# SimulatorT2InterfaceRevD.net
KiCad netlist of a schematic drawn in EAGLE
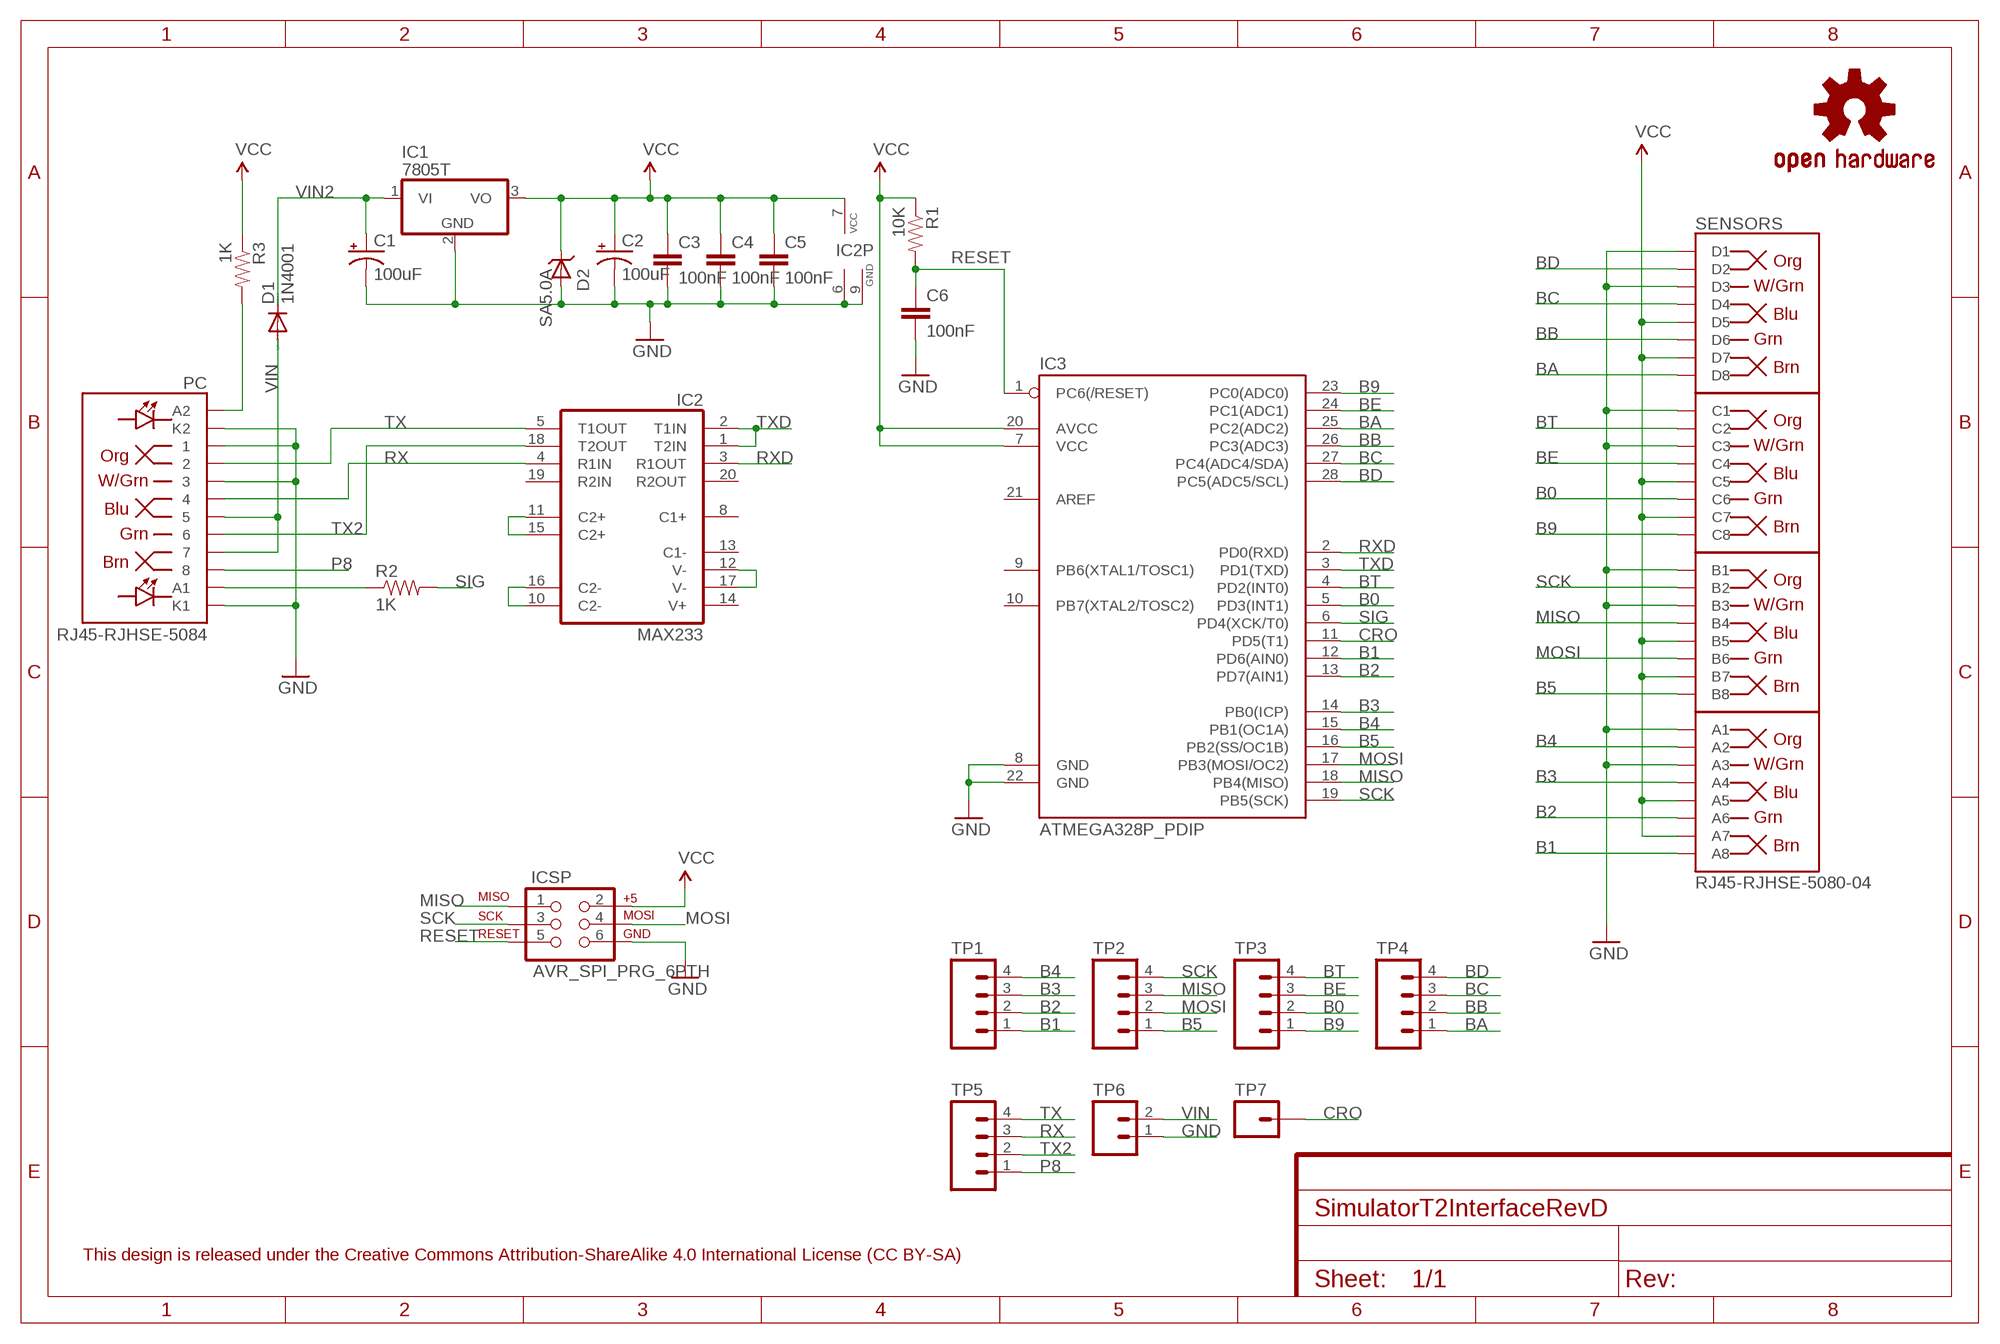
[diagram p0: schematic, sheet 1]

(export (version "E")
  (design (tool "Eeschema 10.0.6"))
  (components
    (comp (ref "C1")
      (value "100uF")
      (footprint "eagle-import:CPOL-RADIAL-100UF-25V")
      (libsource (lib "eagle-import") (part "CAP_POLPTH1"))
    )
    (comp (ref "C2")
      (value "100uF")
      (footprint "eagle-import:CPOL-RADIAL-100UF-25V")
      (libsource (lib "eagle-import") (part "CAP_POLPTH1"))
    )
    (comp (ref "C3")
      (value "100nF")
      (footprint "eagle-import:CAP-PTH-SMALL")
      (libsource (lib "eagle-import") (part "CAPPTH"))
    )
    (comp (ref "C4")
      (value "100nF")
      (footprint "eagle-import:CAP-PTH-SMALL")
      (libsource (lib "eagle-import") (part "CAPPTH"))
    )
    (comp (ref "C5")
      (value "100nF")
      (footprint "eagle-import:CAP-PTH-SMALL")
      (libsource (lib "eagle-import") (part "CAPPTH"))
    )
    (comp (ref "C6")
      (value "100nF")
      (footprint "eagle-import:CAP-PTH-SMALL")
      (libsource (lib "eagle-import") (part "CAPPTH"))
    )
    (comp (ref "D1")
      (value "1N4001")
      (footprint "eagle-import:DO41_DIODE")
      (libsource (lib "eagle-import") (part "1N4001"))
    )
    (comp (ref "D2")
      (value "SA5.0A")
      (footprint "eagle-import:DO41_TVS_UNI")
      (libsource (lib "eagle-import") (part "SA5.0A"))
    )
    (comp (ref "IC1")
      (value "7805T")
      (footprint "eagle-import:TO220H+TSR")
      (libsource (lib "eagle-import") (part "7805T"))
    )
    (comp (ref "IC2")
      (value "MAX233")
      (footprint "eagle-import:DIL20")
      (fields (field (name "MPN") "MAX233ACPP+G36"))
      (libsource (lib "eagle-import") (part "MAX233"))
    )
    (comp (ref "IC3")
      (value "ATMEGA328P_PDIP")
      (footprint "eagle-import:DIL28-3")
      (libsource (lib "eagle-import") (part "ATMEGA328P_PDIP"))
    )
    (comp (ref "ICSP")
      (value "AVR_SPI_PRG_6PTH")
      (footprint "eagle-import:2X3")
      (libsource (lib "eagle-import") (part "AVR_SPI_PRG_6PTH"))
    )
    (comp (ref "LOGO1")
      (value "OSHW-LOGOS")
      (footprint "eagle-import:OSHW-LOGO-S")
      (libsource (lib "eagle-import") (part "OSHW-LOGOS"))
    )
    (comp (ref "PC")
      (value "RJ45-RJHSE-5084")
      (footprint "eagle-import:RJ45-RJHSE-5084")
      (libsource (lib "eagle-import") (part "RJ45-RJHSE-5084"))
    )
    (comp (ref "R1")
      (value "10K")
      (footprint "eagle-import:AXIAL-0.4")
      (libsource (lib "eagle-import") (part "RESISTORPTH-1/4W"))
    )
    (comp (ref "R2")
      (value "1K")
      (footprint "eagle-import:AXIAL-0.4")
      (libsource (lib "eagle-import") (part "RESISTORPTH-1/4W"))
    )
    (comp (ref "R3")
      (value "1K")
      (footprint "eagle-import:AXIAL-0.4")
      (libsource (lib "eagle-import") (part "RESISTORPTH-1/4W"))
    )
    (comp (ref "SENSORS")
      (value "RJ45-RJHSE-5080-04")
      (footprint "eagle-import:RJ45-RJHSE-5080-04")
      (libsource (lib "eagle-import") (part "RJ45-RJHSE-5080-04"))
    )
    (comp (ref "TP1")
      (value "M04PTH")
      (footprint "eagle-import:1X04")
      (libsource (lib "eagle-import") (part "M04PTH"))
    )
    (comp (ref "TP2")
      (value "M04PTH")
      (footprint "eagle-import:1X04")
      (libsource (lib "eagle-import") (part "M04PTH"))
    )
    (comp (ref "TP3")
      (value "M04PTH")
      (footprint "eagle-import:1X04")
      (libsource (lib "eagle-import") (part "M04PTH"))
    )
    (comp (ref "TP4")
      (value "M04PTH")
      (footprint "eagle-import:1X04")
      (libsource (lib "eagle-import") (part "M04PTH"))
    )
    (comp (ref "TP5")
      (value "M04PTH")
      (footprint "eagle-import:1X04")
      (libsource (lib "eagle-import") (part "M04PTH"))
    )
    (comp (ref "TP6")
      (value "M02PTH")
      (footprint "eagle-import:1X02")
      (libsource (lib "eagle-import") (part "M02PTH"))
    )
    (comp (ref "TP7")
      (value "M01PTH")
      (footprint "eagle-import:1X01")
      (libsource (lib "eagle-import") (part "M01PTH"))
    )
  )
  (nets
    (net (code "1") (name "/B0") (class "Default")
      (node (ref "IC3") (pin "5") (pinfunction "PD3(INT1)_5") (pintype "bidirectional"))
      (node (ref "SENSORS") (pin "C6") (pinfunction "C6_C6") (pintype "bidirectional"))
      (node (ref "TP3") (pin "2") (pinfunction "2_2") (pintype "passive"))
    )
    (net (code "2") (name "/B1") (class "Default")
      (node (ref "IC3") (pin "12") (pinfunction "PD6(AIN0)_12") (pintype "bidirectional"))
      (node (ref "SENSORS") (pin "A8") (pinfunction "A8_A8") (pintype "bidirectional"))
      (node (ref "TP1") (pin "1") (pinfunction "1_1") (pintype "passive"))
    )
    (net (code "3") (name "/B2") (class "Default")
      (node (ref "IC3") (pin "13") (pinfunction "PD7(AIN1)_13") (pintype "bidirectional"))
      (node (ref "SENSORS") (pin "A6") (pinfunction "A6_A6") (pintype "bidirectional"))
      (node (ref "TP1") (pin "2") (pinfunction "2_2") (pintype "passive"))
    )
    (net (code "4") (name "/B3") (class "Default")
      (node (ref "IC3") (pin "14") (pinfunction "PB0(ICP)_14") (pintype "bidirectional"))
      (node (ref "SENSORS") (pin "A4") (pinfunction "A4_A4") (pintype "bidirectional"))
      (node (ref "TP1") (pin "3") (pinfunction "3_3") (pintype "passive"))
    )
    (net (code "5") (name "/B4") (class "Default")
      (node (ref "IC3") (pin "15") (pinfunction "PB1(OC1A)_15") (pintype "bidirectional"))
      (node (ref "SENSORS") (pin "A2") (pinfunction "A2_A2") (pintype "bidirectional"))
      (node (ref "TP1") (pin "4") (pinfunction "4_4") (pintype "passive"))
    )
    (net (code "6") (name "/B5") (class "Default")
      (node (ref "IC3") (pin "16") (pinfunction "PB2(SS/OC1B)_16") (pintype "bidirectional"))
      (node (ref "SENSORS") (pin "B8") (pinfunction "B8_B8") (pintype "bidirectional"))
      (node (ref "TP2") (pin "1") (pinfunction "1_1") (pintype "passive"))
    )
    (net (code "7") (name "/B9") (class "Default")
      (node (ref "IC3") (pin "23") (pinfunction "PC0(ADC0)_23") (pintype "bidirectional"))
      (node (ref "SENSORS") (pin "C8") (pinfunction "C8_C8") (pintype "bidirectional"))
      (node (ref "TP3") (pin "1") (pinfunction "1_1") (pintype "passive"))
    )
    (net (code "8") (name "/BA") (class "Default")
      (node (ref "IC3") (pin "25") (pinfunction "PC2(ADC2)_25") (pintype "bidirectional"))
      (node (ref "SENSORS") (pin "D8") (pinfunction "D8_D8") (pintype "bidirectional"))
      (node (ref "TP4") (pin "1") (pinfunction "1_1") (pintype "passive"))
    )
    (net (code "9") (name "/BB") (class "Default")
      (node (ref "IC3") (pin "26") (pinfunction "PC3(ADC3)_26") (pintype "bidirectional"))
      (node (ref "SENSORS") (pin "D6") (pinfunction "D6_D6") (pintype "bidirectional"))
      (node (ref "TP4") (pin "2") (pinfunction "2_2") (pintype "passive"))
    )
    (net (code "10") (name "/BC") (class "Default")
      (node (ref "IC3") (pin "27") (pinfunction "PC4(ADC4/SDA)_27") (pintype "bidirectional"))
      (node (ref "SENSORS") (pin "D4") (pinfunction "D4_D4") (pintype "bidirectional"))
      (node (ref "TP4") (pin "3") (pinfunction "3_3") (pintype "passive"))
    )
    (net (code "11") (name "/BD") (class "Default")
      (node (ref "IC3") (pin "28") (pinfunction "PC5(ADC5/SCL)_28") (pintype "bidirectional"))
      (node (ref "SENSORS") (pin "D2") (pinfunction "D2_D2") (pintype "bidirectional"))
      (node (ref "TP4") (pin "4") (pinfunction "4_4") (pintype "passive"))
    )
    (net (code "12") (name "/BE") (class "Default")
      (node (ref "IC3") (pin "24") (pinfunction "PC1(ADC1)_24") (pintype "bidirectional"))
      (node (ref "SENSORS") (pin "C4") (pinfunction "C4_C4") (pintype "bidirectional"))
      (node (ref "TP3") (pin "3") (pinfunction "3_3") (pintype "passive"))
    )
    (net (code "13") (name "/BT") (class "Default")
      (node (ref "IC3") (pin "4") (pinfunction "PD2(INT0)_4") (pintype "bidirectional"))
      (node (ref "SENSORS") (pin "C2") (pinfunction "C2_C2") (pintype "bidirectional"))
      (node (ref "TP3") (pin "4") (pinfunction "4_4") (pintype "passive"))
    )
    (net (code "14") (name "/CRO") (class "Default")
      (node (ref "IC3") (pin "11") (pinfunction "PD5(T1)_11") (pintype "bidirectional"))
      (node (ref "TP7") (pin "1") (pinfunction "1_1") (pintype "passive"))
    )
    (net (code "15") (name "/MISO") (class "Default")
      (node (ref "IC3") (pin "18") (pinfunction "PB4(MISO)_18") (pintype "bidirectional"))
      (node (ref "ICSP") (pin "1") (pinfunction "1_1") (pintype "passive"))
      (node (ref "SENSORS") (pin "B4") (pinfunction "B4_B4") (pintype "bidirectional"))
      (node (ref "TP2") (pin "3") (pinfunction "3_3") (pintype "passive"))
    )
    (net (code "16") (name "/MOSI") (class "Default")
      (node (ref "IC3") (pin "17") (pinfunction "PB3(MOSI/OC2)_17") (pintype "bidirectional"))
      (node (ref "ICSP") (pin "4") (pinfunction "4_4") (pintype "passive"))
      (node (ref "SENSORS") (pin "B6") (pinfunction "B6_B6") (pintype "bidirectional"))
      (node (ref "TP2") (pin "2") (pinfunction "2_2") (pintype "passive"))
    )
    (net (code "17") (name "/P8") (class "Default")
      (node (ref "PC") (pin "8") (pinfunction "8_8") (pintype "bidirectional"))
      (node (ref "TP5") (pin "1") (pinfunction "1_1") (pintype "passive"))
    )
    (net (code "18") (name "/RESET") (class "Default")
      (node (ref "C6") (pin "1") (pinfunction "1_1") (pintype "passive"))
      (node (ref "IC3") (pin "1") (pinfunction "PC6(/RESET)_1") (pintype "bidirectional"))
      (node (ref "ICSP") (pin "5") (pinfunction "5_5") (pintype "passive"))
      (node (ref "R1") (pin "P$2") (pinfunction "2_P$2") (pintype "passive"))
    )
    (net (code "19") (name "/RX") (class "Default")
      (node (ref "IC2") (pin "4") (pinfunction "R1IN_4") (pintype "input"))
      (node (ref "PC") (pin "4") (pinfunction "4_4") (pintype "bidirectional"))
      (node (ref "TP5") (pin "3") (pinfunction "3_3") (pintype "passive"))
    )
    (net (code "20") (name "/RXD") (class "Default")
      (node (ref "IC2") (pin "3") (pinfunction "R1OUT_3") (pintype "output"))
      (node (ref "IC3") (pin "2") (pinfunction "PD0(RXD)_2") (pintype "bidirectional"))
    )
    (net (code "21") (name "/SCK") (class "Default")
      (node (ref "IC3") (pin "19") (pinfunction "PB5(SCK)_19") (pintype "bidirectional"))
      (node (ref "ICSP") (pin "3") (pinfunction "3_3") (pintype "passive"))
      (node (ref "SENSORS") (pin "B2") (pinfunction "B2_B2") (pintype "bidirectional"))
      (node (ref "TP2") (pin "4") (pinfunction "4_4") (pintype "passive"))
    )
    (net (code "22") (name "/SIG") (class "Default")
      (node (ref "IC3") (pin "6") (pinfunction "PD4(XCK/T0)_6") (pintype "bidirectional"))
      (node (ref "R2") (pin "P$2") (pinfunction "2_P$2") (pintype "passive"))
    )
    (net (code "23") (name "/TX") (class "Default")
      (node (ref "IC2") (pin "5") (pinfunction "T1OUT_5") (pintype "output"))
      (node (ref "PC") (pin "2") (pinfunction "2_2") (pintype "bidirectional"))
      (node (ref "TP5") (pin "4") (pinfunction "4_4") (pintype "passive"))
    )
    (net (code "24") (name "/TX2") (class "Default")
      (node (ref "IC2") (pin "18") (pinfunction "T2OUT_18") (pintype "output"))
      (node (ref "PC") (pin "6") (pinfunction "6_6") (pintype "bidirectional"))
      (node (ref "TP5") (pin "2") (pinfunction "2_2") (pintype "passive"))
    )
    (net (code "25") (name "/TXD") (class "Default")
      (node (ref "IC2") (pin "1") (pinfunction "T2IN_1") (pintype "input"))
      (node (ref "IC2") (pin "2") (pinfunction "T1IN_2") (pintype "input"))
      (node (ref "IC3") (pin "3") (pinfunction "PD1(TXD)_3") (pintype "bidirectional"))
    )
    (net (code "26") (name "/VIN") (class "Default")
      (node (ref "D1") (pin "A") (pinfunction "A_A") (pintype "passive"))
      (node (ref "PC") (pin "5") (pinfunction "5_5") (pintype "bidirectional"))
      (node (ref "PC") (pin "7") (pinfunction "7_7") (pintype "bidirectional"))
      (node (ref "TP6") (pin "2") (pinfunction "2_2") (pintype "passive"))
    )
    (net (code "27") (name "/VIN2") (class "Default")
      (node (ref "C1") (pin "1") (pinfunction "+_1") (pintype "passive"))
      (node (ref "D1") (pin "C") (pinfunction "C_C") (pintype "passive"))
      (node (ref "IC1") (pin "1") (pinfunction "VI_1") (pintype "input"))
    )
    (net (code "28") (name "GND") (class "Default")
      (node (ref "C1") (pin "2") (pinfunction "-_2") (pintype "passive"))
      (node (ref "C2") (pin "2") (pinfunction "-_2") (pintype "passive"))
      (node (ref "C3") (pin "2") (pinfunction "2_2") (pintype "passive"))
      (node (ref "C4") (pin "2") (pinfunction "2_2") (pintype "passive"))
      (node (ref "C5") (pin "2") (pinfunction "2_2") (pintype "passive"))
      (node (ref "C6") (pin "2") (pinfunction "2_2") (pintype "passive"))
      (node (ref "D2") (pin "ANODE") (pinfunction "ANODE_ANODE") (pintype "passive"))
      (node (ref "IC1") (pin "2") (pinfunction "GND_2") (pintype "passive"))
      (node (ref "IC2") (pin "6") (pinfunction "GND_6") (pintype "power_in"))
      (node (ref "IC2") (pin "9") (pinfunction "GND_9") (pintype "power_in"))
      (node (ref "IC3") (pin "22") (pinfunction "GND_22") (pintype "bidirectional"))
      (node (ref "IC3") (pin "8") (pinfunction "GND_8") (pintype "bidirectional"))
      (node (ref "ICSP") (pin "6") (pinfunction "6_6") (pintype "passive"))
      (node (ref "PC") (pin "1") (pinfunction "1_1") (pintype "bidirectional"))
      (node (ref "PC") (pin "3") (pinfunction "3_3") (pintype "bidirectional"))
      (node (ref "PC") (pin "K1") (pinfunction "K1_K1") (pintype "passive"))
      (node (ref "PC") (pin "K2") (pinfunction "K2_K2") (pintype "passive"))
      (node (ref "SENSORS") (pin "A1") (pinfunction "A1_A1") (pintype "bidirectional"))
      (node (ref "SENSORS") (pin "A3") (pinfunction "A3_A3") (pintype "bidirectional"))
      (node (ref "SENSORS") (pin "B1") (pinfunction "B1_B1") (pintype "bidirectional"))
      (node (ref "SENSORS") (pin "B3") (pinfunction "B3_B3") (pintype "bidirectional"))
      (node (ref "SENSORS") (pin "C1") (pinfunction "C1_C1") (pintype "bidirectional"))
      (node (ref "SENSORS") (pin "C3") (pinfunction "C3_C3") (pintype "bidirectional"))
      (node (ref "SENSORS") (pin "D1") (pinfunction "D1_D1") (pintype "bidirectional"))
      (node (ref "SENSORS") (pin "D3") (pinfunction "D3_D3") (pintype "bidirectional"))
      (node (ref "TP6") (pin "1") (pinfunction "1_1") (pintype "passive"))
    )
    (net (code "29") (name "Net-(IC2A-C2+-Pad11)") (class "Default")
      (node (ref "IC2") (pin "11") (pinfunction "C2+_11") (pintype "bidirectional"))
      (node (ref "IC2") (pin "15") (pinfunction "C2+_15") (pintype "bidirectional"))
    )
    (net (code "30") (name "Net-(IC2A-C2--Pad10)") (class "Default")
      (node (ref "IC2") (pin "10") (pinfunction "C2-_10") (pintype "bidirectional"))
      (node (ref "IC2") (pin "16") (pinfunction "C2-_16") (pintype "bidirectional"))
    )
    (net (code "31") (name "Net-(IC2A-V--Pad12)") (class "Default")
      (node (ref "IC2") (pin "12") (pinfunction "V-_12") (pintype "bidirectional"))
      (node (ref "IC2") (pin "17") (pinfunction "V-_17") (pintype "bidirectional"))
    )
    (net (code "32") (name "Net-(R2-1)") (class "Default")
      (node (ref "PC") (pin "A1") (pinfunction "A1_A1") (pintype "passive"))
      (node (ref "R2") (pin "P$1") (pinfunction "1_P$1") (pintype "passive"))
    )
    (net (code "33") (name "Net-(R3-2)") (class "Default")
      (node (ref "PC") (pin "A2") (pinfunction "A2_A2") (pintype "passive"))
      (node (ref "R3") (pin "P$2") (pinfunction "2_P$2") (pintype "passive"))
    )
    (net (code "34") (name "VCC") (class "Default")
      (node (ref "C2") (pin "1") (pinfunction "+_1") (pintype "passive"))
      (node (ref "C3") (pin "1") (pinfunction "1_1") (pintype "passive"))
      (node (ref "C4") (pin "1") (pinfunction "1_1") (pintype "passive"))
      (node (ref "C5") (pin "1") (pinfunction "1_1") (pintype "passive"))
      (node (ref "D2") (pin "CATHODE") (pinfunction "CATHODE_CATHODE") (pintype "passive"))
      (node (ref "IC1") (pin "3") (pinfunction "VO_3") (pintype "passive"))
      (node (ref "IC2") (pin "7") (pinfunction "VCC_7") (pintype "power_in"))
      (node (ref "IC3") (pin "20") (pinfunction "AVCC_20") (pintype "bidirectional"))
      (node (ref "IC3") (pin "7") (pinfunction "VCC_7") (pintype "bidirectional"))
      (node (ref "ICSP") (pin "2") (pinfunction "2_2") (pintype "passive"))
      (node (ref "R1") (pin "P$1") (pinfunction "1_P$1") (pintype "passive"))
      (node (ref "R3") (pin "P$1") (pinfunction "1_P$1") (pintype "passive"))
      (node (ref "SENSORS") (pin "A5") (pinfunction "A5_A5") (pintype "bidirectional"))
      (node (ref "SENSORS") (pin "A7") (pinfunction "A7_A7") (pintype "bidirectional"))
      (node (ref "SENSORS") (pin "B5") (pinfunction "B5_B5") (pintype "bidirectional"))
      (node (ref "SENSORS") (pin "B7") (pinfunction "B7_B7") (pintype "bidirectional"))
      (node (ref "SENSORS") (pin "C5") (pinfunction "C5_C5") (pintype "bidirectional"))
      (node (ref "SENSORS") (pin "C7") (pinfunction "C7_C7") (pintype "bidirectional"))
      (node (ref "SENSORS") (pin "D5") (pinfunction "D5_D5") (pintype "bidirectional"))
      (node (ref "SENSORS") (pin "D7") (pinfunction "D7_D7") (pintype "bidirectional"))
    )
    (net (code "35") (name "unconnected-(IC2A-C1+-Pad8)") (class "Default")
      (node (ref "IC2") (pin "8") (pinfunction "C1+_8") (pintype "bidirectional"))
    )
    (net (code "36") (name "unconnected-(IC2A-C1--Pad13)") (class "Default")
      (node (ref "IC2") (pin "13") (pinfunction "C1-_13") (pintype "bidirectional"))
    )
    (net (code "37") (name "unconnected-(IC2A-R2IN-Pad19)") (class "Default")
      (node (ref "IC2") (pin "19") (pinfunction "R2IN_19") (pintype "input"))
    )
    (net (code "38") (name "unconnected-(IC2A-R2OUT-Pad20)") (class "Default")
      (node (ref "IC2") (pin "20") (pinfunction "R2OUT_20") (pintype "output"))
    )
    (net (code "39") (name "unconnected-(IC2A-V+-Pad14)") (class "Default")
      (node (ref "IC2") (pin "14") (pinfunction "V+_14") (pintype "bidirectional"))
    )
    (net (code "40") (name "unconnected-(IC3-AREF-Pad21)") (class "Default")
      (node (ref "IC3") (pin "21") (pinfunction "AREF_21") (pintype "bidirectional"))
    )
    (net (code "41") (name "unconnected-(IC3-PB6(XTAL1{slash}TOSC1)-Pad9)") (class "Default")
      (node (ref "IC3") (pin "9") (pinfunction "PB6(XTAL1/TOSC1)_9") (pintype "bidirectional"))
    )
    (net (code "42") (name "unconnected-(IC3-PB7(XTAL2{slash}TOSC2)-Pad10)") (class "Default")
      (node (ref "IC3") (pin "10") (pinfunction "PB7(XTAL2/TOSC2)_10") (pintype "bidirectional"))
    )
  )
)
